# invamp.net
KiCad netlist of a schematic drawn in EAGLE
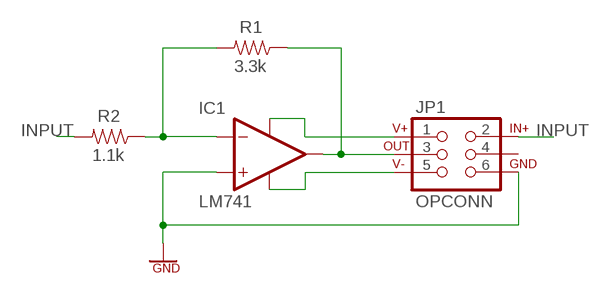
[diagram p0: schematic, sheet 1]

(export (version "E")
  (design (tool "Eeschema 10.0.6"))
  (components
    (comp (ref "IC1")
      (value "LM741")
      (footprint "eagle-import:SO08")
      (libsource (lib "eagle-import") (part "LM741"))
    )
    (comp (ref "JP1")
      (value "OPCONN")
      (footprint "eagle-import:2X3")
      (libsource (lib "eagle-import") (part "OPCONN"))
    )
    (comp (ref "R1")
      (value "3.3k")
      (footprint "eagle-import:SMD0603")
      (libsource (lib "eagle-import") (part "RES_0603"))
    )
    (comp (ref "R2")
      (value "1.1k")
      (footprint "eagle-import:SMD0603")
      (libsource (lib "eagle-import") (part "RES_0603"))
    )
  )
  (nets
    (net (code "1") (name "/INPUT") (class "Default")
      (node (ref "JP1") (pin "2") (pinfunction "2_2") (pintype "passive"))
      (node (ref "R2") (pin "2") (pinfunction "2_2") (pintype "passive"))
    )
    (net (code "2") (name "GND") (class "Default")
      (node (ref "IC1") (pin "3") (pinfunction "IN+_3") (pintype "input"))
      (node (ref "JP1") (pin "6") (pinfunction "6_6") (pintype "passive"))
    )
    (net (code "3") (name "Net-(IC1-IN-)") (class "Default")
      (node (ref "IC1") (pin "2") (pinfunction "IN-_2") (pintype "input"))
      (node (ref "R1") (pin "2") (pinfunction "2_2") (pintype "passive"))
      (node (ref "R2") (pin "1") (pinfunction "1_1") (pintype "passive"))
    )
    (net (code "4") (name "Net-(IC1-OUT)") (class "Default")
      (node (ref "IC1") (pin "6") (pinfunction "OUT_6") (pintype "output"))
      (node (ref "JP1") (pin "3") (pinfunction "3_3") (pintype "passive"))
      (node (ref "R1") (pin "1") (pinfunction "1_1") (pintype "passive"))
    )
    (net (code "5") (name "Net-(IC1-V+)") (class "Default")
      (node (ref "IC1") (pin "7") (pinfunction "V+_7") (pintype "power_in"))
      (node (ref "JP1") (pin "1") (pinfunction "1_1") (pintype "passive"))
    )
    (net (code "6") (name "Net-(IC1-V-)") (class "Default")
      (node (ref "IC1") (pin "4") (pinfunction "V-_4") (pintype "power_in"))
      (node (ref "JP1") (pin "5") (pinfunction "5_5") (pintype "passive"))
    )
    (net (code "7") (name "unconnected-(JP1-Pad4)") (class "Default")
      (node (ref "JP1") (pin "4") (pinfunction "4_4") (pintype "passive"))
    )
  )
)
